# OpenArt_v1_4.net
KiCad netlist of a schematic drawn in EasyEDA Pro
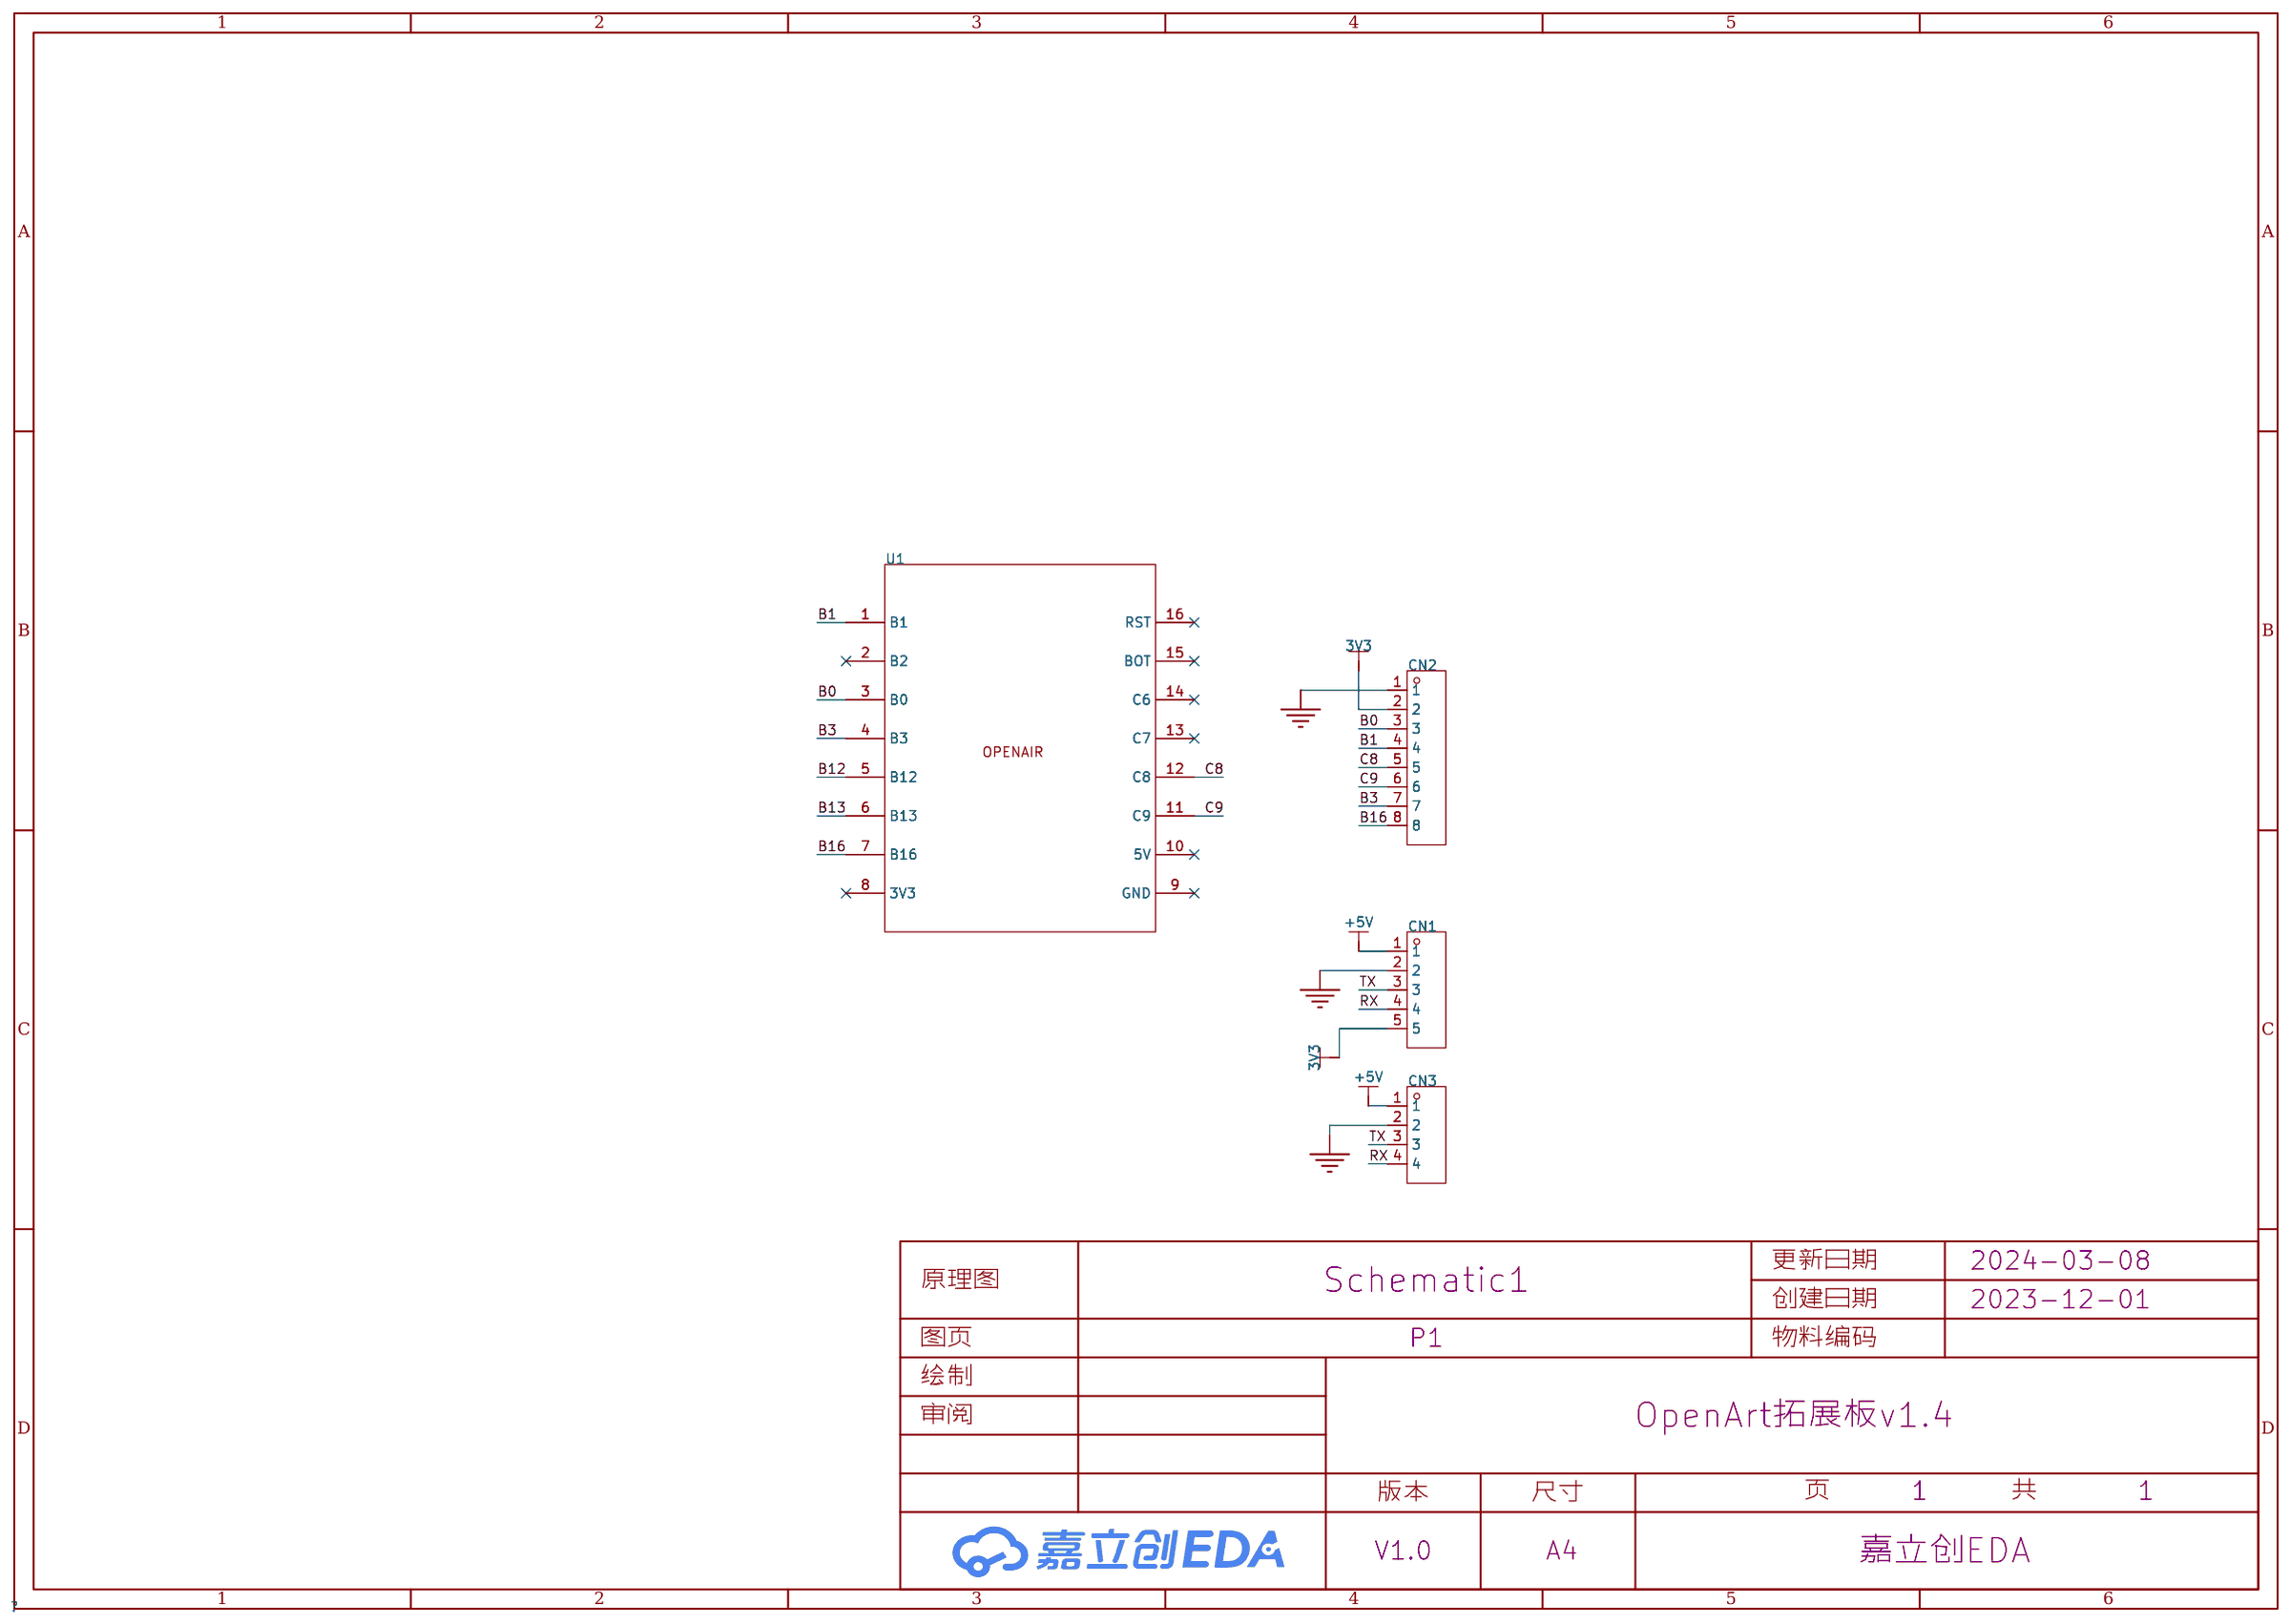
[diagram p0: schematic sheet]

(export (version "E")
  (design (tool "Eeschema 10.0.6"))
  (components
    (comp (ref "CN1")
      (value "ZX-HA2.54-5PWZ")
      (footprint "easyedapro:CONN-TH_5P-P2.50_ZX-HA2.54-5PWZ")
      (fields (field (name "Manufacturer") "Megastar(兆星)"))
      (libsource (lib "easyedapro") (part "ZX-HA2.54-5PWZ"))
    )
    (comp (ref "CN2")
      (value "BX-XH2.54-8PZZ")
      (footprint "easyedapro:CONN-TH_8P-P2.50_BX-XH2.54-8PZZ")
      (fields (field (name "Manufacturer") "Bossie(博锡)"))
      (libsource (lib "easyedapro") (part "BX-XH2.54-8PZZ"))
    )
    (comp (ref "CN3")
      (value "ZX-XH2.54-4PWZ")
      (footprint "easyedapro:CONN-TH_4P-P2.50_ZX-XH2.54-4PWZ")
      (fields (field (name "Manufacturer") "Megastar(兆星)"))
      (libsource (lib "easyedapro") (part "ZX-XH2.54-4PWZ"))
    )
    (comp (ref "U1") (value "~") (libsource (lib "easyedapro") (part "OPENAIR")))
  )
  (nets
    (net (code "1") (name "+5V") (class "Default")
      (node (ref "CN1") (pin "1") (pinfunction "1_1") (pintype "unspecified"))
      (node (ref "CN3") (pin "1") (pinfunction "1_1") (pintype "unspecified"))
    )
    (net (code "2") (name "/B0") (class "Default")
      (node (ref "CN2") (pin "3") (pinfunction "3_3") (pintype "unspecified"))
      (node (ref "U1") (pin "3") (pinfunction "B0_3") (pintype "input"))
    )
    (net (code "3") (name "/B1") (class "Default")
      (node (ref "CN2") (pin "4") (pinfunction "4_4") (pintype "unspecified"))
      (node (ref "U1") (pin "1") (pinfunction "B1_1") (pintype "input"))
    )
    (net (code "4") (name "/B3") (class "Default")
      (node (ref "CN2") (pin "7") (pinfunction "7_7") (pintype "unspecified"))
      (node (ref "U1") (pin "4") (pinfunction "B3_4") (pintype "input"))
    )
    (net (code "5") (name "/B12") (class "Default")
      (node (ref "U1") (pin "5") (pinfunction "B12_5") (pintype "input"))
    )
    (net (code "6") (name "/B13") (class "Default")
      (node (ref "U1") (pin "6") (pinfunction "B13_6") (pintype "input"))
    )
    (net (code "7") (name "/B16") (class "Default")
      (node (ref "CN2") (pin "8") (pinfunction "8_8") (pintype "unspecified"))
      (node (ref "U1") (pin "7") (pinfunction "B16_7") (pintype "input"))
    )
    (net (code "8") (name "/C8") (class "Default")
      (node (ref "CN2") (pin "5") (pinfunction "5_5") (pintype "unspecified"))
      (node (ref "U1") (pin "12") (pinfunction "C8_12") (pintype "input"))
    )
    (net (code "9") (name "/C9") (class "Default")
      (node (ref "CN2") (pin "6") (pinfunction "6_6") (pintype "unspecified"))
      (node (ref "U1") (pin "11") (pinfunction "C9_11") (pintype "input"))
    )
    (net (code "10") (name "/RX") (class "Default")
      (node (ref "CN1") (pin "4") (pinfunction "4_4") (pintype "unspecified"))
      (node (ref "CN3") (pin "4") (pinfunction "4_4") (pintype "unspecified"))
    )
    (net (code "11") (name "/TX") (class "Default")
      (node (ref "CN1") (pin "3") (pinfunction "3_3") (pintype "unspecified"))
      (node (ref "CN3") (pin "3") (pinfunction "3_3") (pintype "unspecified"))
    )
    (net (code "12") (name "3V3") (class "Default")
      (node (ref "CN1") (pin "5") (pinfunction "5_5") (pintype "unspecified"))
      (node (ref "CN2") (pin "2") (pinfunction "2_2") (pintype "unspecified"))
    )
    (net (code "13") (name "GND") (class "Default")
      (node (ref "CN1") (pin "2") (pinfunction "2_2") (pintype "unspecified"))
      (node (ref "CN2") (pin "1") (pinfunction "1_1") (pintype "unspecified"))
      (node (ref "CN3") (pin "2") (pinfunction "2_2") (pintype "unspecified"))
    )
    (net (code "14") (name "unconnected-(U1-3V3-Pad8)") (class "Default")
      (node (ref "U1") (pin "8") (pinfunction "3V3_8") (pintype "input+no_connect"))
    )
    (net (code "15") (name "unconnected-(U1-5V-Pad10)") (class "Default")
      (node (ref "U1") (pin "10") (pinfunction "5V_10") (pintype "input+no_connect"))
    )
    (net (code "16") (name "unconnected-(U1-B2-Pad2)") (class "Default")
      (node (ref "U1") (pin "2") (pinfunction "B2_2") (pintype "input+no_connect"))
    )
    (net (code "17") (name "unconnected-(U1-BOT-Pad15)") (class "Default")
      (node (ref "U1") (pin "15") (pinfunction "BOT_15") (pintype "input+no_connect"))
    )
    (net (code "18") (name "unconnected-(U1-C6-Pad14)") (class "Default")
      (node (ref "U1") (pin "14") (pinfunction "C6_14") (pintype "input+no_connect"))
    )
    (net (code "19") (name "unconnected-(U1-C7-Pad13)") (class "Default")
      (node (ref "U1") (pin "13") (pinfunction "C7_13") (pintype "input+no_connect"))
    )
    (net (code "20") (name "unconnected-(U1-GND-Pad9)") (class "Default")
      (node (ref "U1") (pin "9") (pinfunction "GND_9") (pintype "input+no_connect"))
    )
    (net (code "21") (name "unconnected-(U1-RST-Pad16)") (class "Default")
      (node (ref "U1") (pin "16") (pinfunction "RST_16") (pintype "input+no_connect"))
    )
  )
)
